# bff-stm32f4-codec.net
KiCad netlist of a schematic drawn in EAGLE
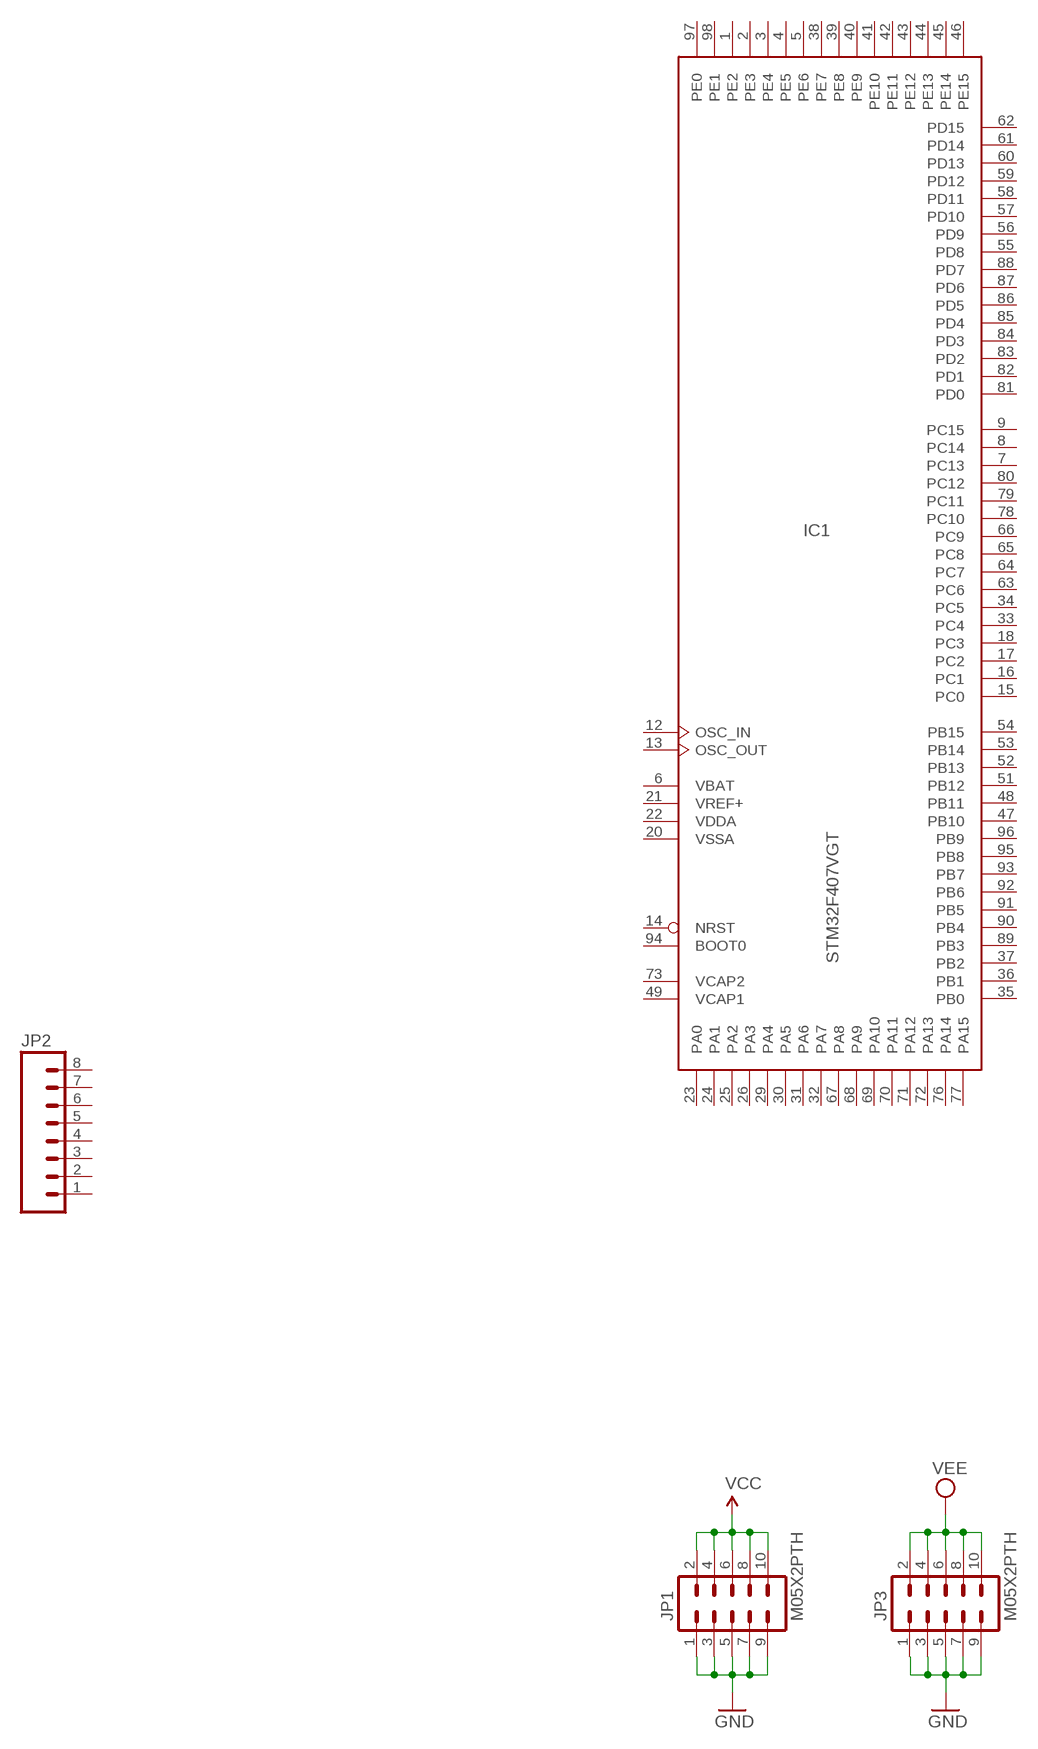
[diagram p0: schematic, sheet 1]

(export (version "E")
  (design (tool "Eeschema 10.0.6"))
  (components
    (comp (ref "IC1")
      (value "STM32F407VGT")
      (footprint "eagle-import:LQFP100")
      (libsource (lib "eagle-import") (part "STM32F407VTG"))
    )
    (comp (ref "JP1")
      (value "M05X2PTH")
      (footprint "eagle-import:AVR_ICSP")
      (libsource (lib "eagle-import") (part "M05X2PTH"))
    )
    (comp (ref "JP2")
      (value "M08")
      (footprint "eagle-import:1X08")
      (libsource (lib "eagle-import") (part "M08"))
    )
    (comp (ref "JP3")
      (value "M05X2PTH")
      (footprint "eagle-import:AVR_ICSP")
      (libsource (lib "eagle-import") (part "M05X2PTH"))
    )
  )
  (nets
    (net (code "1") (name "/VBAT") (class "Default")
      (node (ref "IC1") (pin "6") (pinfunction "VBAT_6") (pintype "power_in"))
    )
    (net (code "2") (name "/VCAP1") (class "Default")
      (node (ref "IC1") (pin "49") (pinfunction "VCAP1_49") (pintype "power_in"))
    )
    (net (code "3") (name "/VCAP2") (class "Default")
      (node (ref "IC1") (pin "73") (pinfunction "VCAP2_73") (pintype "power_in"))
    )
    (net (code "4") (name "/VDDA") (class "Default")
      (node (ref "IC1") (pin "22") (pinfunction "VDDA_22") (pintype "power_in"))
    )
    (net (code "5") (name "/VREF+") (class "Default")
      (node (ref "IC1") (pin "21") (pinfunction "VREF+_21") (pintype "power_in"))
    )
    (net (code "6") (name "/VSSA") (class "Default")
      (node (ref "IC1") (pin "20") (pinfunction "VSSA_20") (pintype "power_in"))
    )
    (net (code "7") (name "GND") (class "Default")
      (node (ref "JP1") (pin "1") (pinfunction "1_1") (pintype "passive"))
      (node (ref "JP1") (pin "3") (pinfunction "3_3") (pintype "passive"))
      (node (ref "JP1") (pin "5") (pinfunction "5_5") (pintype "passive"))
      (node (ref "JP1") (pin "7") (pinfunction "7_7") (pintype "passive"))
      (node (ref "JP1") (pin "9") (pinfunction "9_9") (pintype "passive"))
      (node (ref "JP3") (pin "1") (pinfunction "1_1") (pintype "passive"))
      (node (ref "JP3") (pin "3") (pinfunction "3_3") (pintype "passive"))
      (node (ref "JP3") (pin "5") (pinfunction "5_5") (pintype "passive"))
      (node (ref "JP3") (pin "7") (pinfunction "7_7") (pintype "passive"))
      (node (ref "JP3") (pin "9") (pinfunction "9_9") (pintype "passive"))
    )
    (net (code "8") (name "VCC") (class "Default")
      (node (ref "JP1") (pin "10") (pinfunction "10_10") (pintype "passive"))
      (node (ref "JP1") (pin "2") (pinfunction "2_2") (pintype "passive"))
      (node (ref "JP1") (pin "4") (pinfunction "4_4") (pintype "passive"))
      (node (ref "JP1") (pin "6") (pinfunction "6_6") (pintype "passive"))
      (node (ref "JP1") (pin "8") (pinfunction "8_8") (pintype "passive"))
    )
    (net (code "9") (name "VEE") (class "Default")
      (node (ref "JP3") (pin "10") (pinfunction "10_10") (pintype "passive"))
      (node (ref "JP3") (pin "2") (pinfunction "2_2") (pintype "passive"))
      (node (ref "JP3") (pin "4") (pinfunction "4_4") (pintype "passive"))
      (node (ref "JP3") (pin "6") (pinfunction "6_6") (pintype "passive"))
      (node (ref "JP3") (pin "8") (pinfunction "8_8") (pintype "passive"))
    )
    (net (code "10") (name "unconnected-(IC1A-BOOT0-Pad94)") (class "Default")
      (node (ref "IC1") (pin "94") (pinfunction "BOOT0_94") (pintype "input"))
    )
    (net (code "11") (name "unconnected-(IC1A-NRST-Pad14)") (class "Default")
      (node (ref "IC1") (pin "14") (pinfunction "NRST_14") (pintype "bidirectional"))
    )
    (net (code "12") (name "unconnected-(IC1A-OSC_IN-Pad12)") (class "Default")
      (node (ref "IC1") (pin "12") (pinfunction "OSC_IN_12") (pintype "bidirectional"))
    )
    (net (code "13") (name "unconnected-(IC1A-OSC_OUT-Pad13)") (class "Default")
      (node (ref "IC1") (pin "13") (pinfunction "OSC_OUT_13") (pintype "bidirectional"))
    )
    (net (code "14") (name "unconnected-(IC1A-PA0-Pad23)") (class "Default")
      (node (ref "IC1") (pin "23") (pinfunction "PA0_23") (pintype "bidirectional"))
    )
    (net (code "15") (name "unconnected-(IC1A-PA1-Pad24)") (class "Default")
      (node (ref "IC1") (pin "24") (pinfunction "PA1_24") (pintype "bidirectional"))
    )
    (net (code "16") (name "unconnected-(IC1A-PA2-Pad25)") (class "Default")
      (node (ref "IC1") (pin "25") (pinfunction "PA2_25") (pintype "bidirectional"))
    )
    (net (code "17") (name "unconnected-(IC1A-PA3-Pad26)") (class "Default")
      (node (ref "IC1") (pin "26") (pinfunction "PA3_26") (pintype "bidirectional"))
    )
    (net (code "18") (name "unconnected-(IC1A-PA4-Pad29)") (class "Default")
      (node (ref "IC1") (pin "29") (pinfunction "PA4_29") (pintype "bidirectional"))
    )
    (net (code "19") (name "unconnected-(IC1A-PA5-Pad30)") (class "Default")
      (node (ref "IC1") (pin "30") (pinfunction "PA5_30") (pintype "bidirectional"))
    )
    (net (code "20") (name "unconnected-(IC1A-PA6-Pad31)") (class "Default")
      (node (ref "IC1") (pin "31") (pinfunction "PA6_31") (pintype "bidirectional"))
    )
    (net (code "21") (name "unconnected-(IC1A-PA7-Pad32)") (class "Default")
      (node (ref "IC1") (pin "32") (pinfunction "PA7_32") (pintype "bidirectional"))
    )
    (net (code "22") (name "unconnected-(IC1A-PA8-Pad67)") (class "Default")
      (node (ref "IC1") (pin "67") (pinfunction "PA8_67") (pintype "bidirectional"))
    )
    (net (code "23") (name "unconnected-(IC1A-PA9-Pad68)") (class "Default")
      (node (ref "IC1") (pin "68") (pinfunction "PA9_68") (pintype "bidirectional"))
    )
    (net (code "24") (name "unconnected-(IC1A-PA10-Pad69)") (class "Default")
      (node (ref "IC1") (pin "69") (pinfunction "PA10_69") (pintype "bidirectional"))
    )
    (net (code "25") (name "unconnected-(IC1A-PA11-Pad70)") (class "Default")
      (node (ref "IC1") (pin "70") (pinfunction "PA11_70") (pintype "bidirectional"))
    )
    (net (code "26") (name "unconnected-(IC1A-PA12-Pad71)") (class "Default")
      (node (ref "IC1") (pin "71") (pinfunction "PA12_71") (pintype "bidirectional"))
    )
    (net (code "27") (name "unconnected-(IC1A-PA13-Pad72)") (class "Default")
      (node (ref "IC1") (pin "72") (pinfunction "PA13_72") (pintype "bidirectional"))
    )
    (net (code "28") (name "unconnected-(IC1A-PA14-Pad76)") (class "Default")
      (node (ref "IC1") (pin "76") (pinfunction "PA14_76") (pintype "bidirectional"))
    )
    (net (code "29") (name "unconnected-(IC1A-PA15-Pad77)") (class "Default")
      (node (ref "IC1") (pin "77") (pinfunction "PA15_77") (pintype "bidirectional"))
    )
    (net (code "30") (name "unconnected-(IC1A-PB0-Pad35)") (class "Default")
      (node (ref "IC1") (pin "35") (pinfunction "PB0_35") (pintype "bidirectional"))
    )
    (net (code "31") (name "unconnected-(IC1A-PB1-Pad36)") (class "Default")
      (node (ref "IC1") (pin "36") (pinfunction "PB1_36") (pintype "bidirectional"))
    )
    (net (code "32") (name "unconnected-(IC1A-PB2-Pad37)") (class "Default")
      (node (ref "IC1") (pin "37") (pinfunction "PB2_37") (pintype "bidirectional"))
    )
    (net (code "33") (name "unconnected-(IC1A-PB3-Pad89)") (class "Default")
      (node (ref "IC1") (pin "89") (pinfunction "PB3_89") (pintype "bidirectional"))
    )
    (net (code "34") (name "unconnected-(IC1A-PB4-Pad90)") (class "Default")
      (node (ref "IC1") (pin "90") (pinfunction "PB4_90") (pintype "bidirectional"))
    )
    (net (code "35") (name "unconnected-(IC1A-PB5-Pad91)") (class "Default")
      (node (ref "IC1") (pin "91") (pinfunction "PB5_91") (pintype "bidirectional"))
    )
    (net (code "36") (name "unconnected-(IC1A-PB6-Pad92)") (class "Default")
      (node (ref "IC1") (pin "92") (pinfunction "PB6_92") (pintype "bidirectional"))
    )
    (net (code "37") (name "unconnected-(IC1A-PB7-Pad93)") (class "Default")
      (node (ref "IC1") (pin "93") (pinfunction "PB7_93") (pintype "bidirectional"))
    )
    (net (code "38") (name "unconnected-(IC1A-PB8-Pad95)") (class "Default")
      (node (ref "IC1") (pin "95") (pinfunction "PB8_95") (pintype "bidirectional"))
    )
    (net (code "39") (name "unconnected-(IC1A-PB9-Pad96)") (class "Default")
      (node (ref "IC1") (pin "96") (pinfunction "PB9_96") (pintype "bidirectional"))
    )
    (net (code "40") (name "unconnected-(IC1A-PB10-Pad47)") (class "Default")
      (node (ref "IC1") (pin "47") (pinfunction "PB10_47") (pintype "bidirectional"))
    )
    (net (code "41") (name "unconnected-(IC1A-PB11-Pad48)") (class "Default")
      (node (ref "IC1") (pin "48") (pinfunction "PB11_48") (pintype "bidirectional"))
    )
    (net (code "42") (name "unconnected-(IC1A-PB12-Pad51)") (class "Default")
      (node (ref "IC1") (pin "51") (pinfunction "PB12_51") (pintype "bidirectional"))
    )
    (net (code "43") (name "unconnected-(IC1A-PB13-Pad52)") (class "Default")
      (node (ref "IC1") (pin "52") (pinfunction "PB13_52") (pintype "bidirectional"))
    )
    (net (code "44") (name "unconnected-(IC1A-PB14-Pad53)") (class "Default")
      (node (ref "IC1") (pin "53") (pinfunction "PB14_53") (pintype "bidirectional"))
    )
    (net (code "45") (name "unconnected-(IC1A-PB15-Pad54)") (class "Default")
      (node (ref "IC1") (pin "54") (pinfunction "PB15_54") (pintype "bidirectional"))
    )
    (net (code "46") (name "unconnected-(IC1A-PC0-Pad15)") (class "Default")
      (node (ref "IC1") (pin "15") (pinfunction "PC0_15") (pintype "bidirectional"))
    )
    (net (code "47") (name "unconnected-(IC1A-PC1-Pad16)") (class "Default")
      (node (ref "IC1") (pin "16") (pinfunction "PC1_16") (pintype "bidirectional"))
    )
    (net (code "48") (name "unconnected-(IC1A-PC2-Pad17)") (class "Default")
      (node (ref "IC1") (pin "17") (pinfunction "PC2_17") (pintype "bidirectional"))
    )
    (net (code "49") (name "unconnected-(IC1A-PC3-Pad18)") (class "Default")
      (node (ref "IC1") (pin "18") (pinfunction "PC3_18") (pintype "bidirectional"))
    )
    (net (code "50") (name "unconnected-(IC1A-PC4-Pad33)") (class "Default")
      (node (ref "IC1") (pin "33") (pinfunction "PC4_33") (pintype "bidirectional"))
    )
    (net (code "51") (name "unconnected-(IC1A-PC5-Pad34)") (class "Default")
      (node (ref "IC1") (pin "34") (pinfunction "PC5_34") (pintype "bidirectional"))
    )
    (net (code "52") (name "unconnected-(IC1A-PC6-Pad63)") (class "Default")
      (node (ref "IC1") (pin "63") (pinfunction "PC6_63") (pintype "bidirectional"))
    )
    (net (code "53") (name "unconnected-(IC1A-PC7-Pad64)") (class "Default")
      (node (ref "IC1") (pin "64") (pinfunction "PC7_64") (pintype "bidirectional"))
    )
    (net (code "54") (name "unconnected-(IC1A-PC8-Pad65)") (class "Default")
      (node (ref "IC1") (pin "65") (pinfunction "PC8_65") (pintype "bidirectional"))
    )
    (net (code "55") (name "unconnected-(IC1A-PC9-Pad66)") (class "Default")
      (node (ref "IC1") (pin "66") (pinfunction "PC9_66") (pintype "bidirectional"))
    )
    (net (code "56") (name "unconnected-(IC1A-PC10-Pad78)") (class "Default")
      (node (ref "IC1") (pin "78") (pinfunction "PC10_78") (pintype "bidirectional"))
    )
    (net (code "57") (name "unconnected-(IC1A-PC11-Pad79)") (class "Default")
      (node (ref "IC1") (pin "79") (pinfunction "PC11_79") (pintype "bidirectional"))
    )
    (net (code "58") (name "unconnected-(IC1A-PC12-Pad80)") (class "Default")
      (node (ref "IC1") (pin "80") (pinfunction "PC12_80") (pintype "bidirectional"))
    )
    (net (code "59") (name "unconnected-(IC1A-PC13-Pad7)") (class "Default")
      (node (ref "IC1") (pin "7") (pinfunction "PC13_7") (pintype "bidirectional"))
    )
    (net (code "60") (name "unconnected-(IC1A-PC14-Pad8)") (class "Default")
      (node (ref "IC1") (pin "8") (pinfunction "PC14_8") (pintype "bidirectional"))
    )
    (net (code "61") (name "unconnected-(IC1A-PC15-Pad9)") (class "Default")
      (node (ref "IC1") (pin "9") (pinfunction "PC15_9") (pintype "bidirectional"))
    )
    (net (code "62") (name "unconnected-(IC1A-PD0-Pad81)") (class "Default")
      (node (ref "IC1") (pin "81") (pinfunction "PD0_81") (pintype "bidirectional"))
    )
    (net (code "63") (name "unconnected-(IC1A-PD1-Pad82)") (class "Default")
      (node (ref "IC1") (pin "82") (pinfunction "PD1_82") (pintype "bidirectional"))
    )
    (net (code "64") (name "unconnected-(IC1A-PD2-Pad83)") (class "Default")
      (node (ref "IC1") (pin "83") (pinfunction "PD2_83") (pintype "bidirectional"))
    )
    (net (code "65") (name "unconnected-(IC1A-PD3-Pad84)") (class "Default")
      (node (ref "IC1") (pin "84") (pinfunction "PD3_84") (pintype "bidirectional"))
    )
    (net (code "66") (name "unconnected-(IC1A-PD4-Pad85)") (class "Default")
      (node (ref "IC1") (pin "85") (pinfunction "PD4_85") (pintype "bidirectional"))
    )
    (net (code "67") (name "unconnected-(IC1A-PD5-Pad86)") (class "Default")
      (node (ref "IC1") (pin "86") (pinfunction "PD5_86") (pintype "bidirectional"))
    )
    (net (code "68") (name "unconnected-(IC1A-PD6-Pad87)") (class "Default")
      (node (ref "IC1") (pin "87") (pinfunction "PD6_87") (pintype "bidirectional"))
    )
    (net (code "69") (name "unconnected-(IC1A-PD7-Pad88)") (class "Default")
      (node (ref "IC1") (pin "88") (pinfunction "PD7_88") (pintype "bidirectional"))
    )
    (net (code "70") (name "unconnected-(IC1A-PD8-Pad55)") (class "Default")
      (node (ref "IC1") (pin "55") (pinfunction "PD8_55") (pintype "bidirectional"))
    )
    (net (code "71") (name "unconnected-(IC1A-PD9-Pad56)") (class "Default")
      (node (ref "IC1") (pin "56") (pinfunction "PD9_56") (pintype "bidirectional"))
    )
    (net (code "72") (name "unconnected-(IC1A-PD10-Pad57)") (class "Default")
      (node (ref "IC1") (pin "57") (pinfunction "PD10_57") (pintype "bidirectional"))
    )
    (net (code "73") (name "unconnected-(IC1A-PD11-Pad58)") (class "Default")
      (node (ref "IC1") (pin "58") (pinfunction "PD11_58") (pintype "bidirectional"))
    )
    (net (code "74") (name "unconnected-(IC1A-PD12-Pad59)") (class "Default")
      (node (ref "IC1") (pin "59") (pinfunction "PD12_59") (pintype "bidirectional"))
    )
    (net (code "75") (name "unconnected-(IC1A-PD13-Pad60)") (class "Default")
      (node (ref "IC1") (pin "60") (pinfunction "PD13_60") (pintype "bidirectional"))
    )
    (net (code "76") (name "unconnected-(IC1A-PD14-Pad61)") (class "Default")
      (node (ref "IC1") (pin "61") (pinfunction "PD14_61") (pintype "bidirectional"))
    )
    (net (code "77") (name "unconnected-(IC1A-PD15-Pad62)") (class "Default")
      (node (ref "IC1") (pin "62") (pinfunction "PD15_62") (pintype "bidirectional"))
    )
    (net (code "78") (name "unconnected-(IC1A-PE0-Pad97)") (class "Default")
      (node (ref "IC1") (pin "97") (pinfunction "PE0_97") (pintype "bidirectional"))
    )
    (net (code "79") (name "unconnected-(IC1A-PE1-Pad98)") (class "Default")
      (node (ref "IC1") (pin "98") (pinfunction "PE1_98") (pintype "bidirectional"))
    )
    (net (code "80") (name "unconnected-(IC1A-PE2-Pad1)") (class "Default")
      (node (ref "IC1") (pin "1") (pinfunction "PE2_1") (pintype "bidirectional"))
    )
    (net (code "81") (name "unconnected-(IC1A-PE3-Pad2)") (class "Default")
      (node (ref "IC1") (pin "2") (pinfunction "PE3_2") (pintype "bidirectional"))
    )
    (net (code "82") (name "unconnected-(IC1A-PE4-Pad3)") (class "Default")
      (node (ref "IC1") (pin "3") (pinfunction "PE4_3") (pintype "bidirectional"))
    )
    (net (code "83") (name "unconnected-(IC1A-PE5-Pad4)") (class "Default")
      (node (ref "IC1") (pin "4") (pinfunction "PE5_4") (pintype "bidirectional"))
    )
    (net (code "84") (name "unconnected-(IC1A-PE6-Pad5)") (class "Default")
      (node (ref "IC1") (pin "5") (pinfunction "PE6_5") (pintype "bidirectional"))
    )
    (net (code "85") (name "unconnected-(IC1A-PE7-Pad38)") (class "Default")
      (node (ref "IC1") (pin "38") (pinfunction "PE7_38") (pintype "bidirectional"))
    )
    (net (code "86") (name "unconnected-(IC1A-PE8-Pad39)") (class "Default")
      (node (ref "IC1") (pin "39") (pinfunction "PE8_39") (pintype "bidirectional"))
    )
    (net (code "87") (name "unconnected-(IC1A-PE9-Pad40)") (class "Default")
      (node (ref "IC1") (pin "40") (pinfunction "PE9_40") (pintype "bidirectional"))
    )
    (net (code "88") (name "unconnected-(IC1A-PE10-Pad41)") (class "Default")
      (node (ref "IC1") (pin "41") (pinfunction "PE10_41") (pintype "bidirectional"))
    )
    (net (code "89") (name "unconnected-(IC1A-PE11-Pad42)") (class "Default")
      (node (ref "IC1") (pin "42") (pinfunction "PE11_42") (pintype "bidirectional"))
    )
    (net (code "90") (name "unconnected-(IC1A-PE12-Pad43)") (class "Default")
      (node (ref "IC1") (pin "43") (pinfunction "PE12_43") (pintype "bidirectional"))
    )
    (net (code "91") (name "unconnected-(IC1A-PE13-Pad44)") (class "Default")
      (node (ref "IC1") (pin "44") (pinfunction "PE13_44") (pintype "bidirectional"))
    )
    (net (code "92") (name "unconnected-(IC1A-PE14-Pad45)") (class "Default")
      (node (ref "IC1") (pin "45") (pinfunction "PE14_45") (pintype "bidirectional"))
    )
    (net (code "93") (name "unconnected-(IC1A-PE15-Pad46)") (class "Default")
      (node (ref "IC1") (pin "46") (pinfunction "PE15_46") (pintype "bidirectional"))
    )
    (net (code "94") (name "unconnected-(JP2-Pad1)") (class "Default")
      (node (ref "JP2") (pin "1") (pinfunction "1_1") (pintype "passive"))
    )
    (net (code "95") (name "unconnected-(JP2-Pad2)") (class "Default")
      (node (ref "JP2") (pin "2") (pinfunction "2_2") (pintype "passive"))
    )
    (net (code "96") (name "unconnected-(JP2-Pad3)") (class "Default")
      (node (ref "JP2") (pin "3") (pinfunction "3_3") (pintype "passive"))
    )
    (net (code "97") (name "unconnected-(JP2-Pad4)") (class "Default")
      (node (ref "JP2") (pin "4") (pinfunction "4_4") (pintype "passive"))
    )
    (net (code "98") (name "unconnected-(JP2-Pad5)") (class "Default")
      (node (ref "JP2") (pin "5") (pinfunction "5_5") (pintype "passive"))
    )
    (net (code "99") (name "unconnected-(JP2-Pad6)") (class "Default")
      (node (ref "JP2") (pin "6") (pinfunction "6_6") (pintype "passive"))
    )
    (net (code "100") (name "unconnected-(JP2-Pad7)") (class "Default")
      (node (ref "JP2") (pin "7") (pinfunction "7_7") (pintype "passive"))
    )
    (net (code "101") (name "unconnected-(JP2-Pad8)") (class "Default")
      (node (ref "JP2") (pin "8") (pinfunction "8_8") (pintype "passive"))
    )
  )
)
